# ProPrj_usb_hub_v2_2026-04-0__sche1.net
KiCad netlist of a schematic drawn in EasyEDA Pro
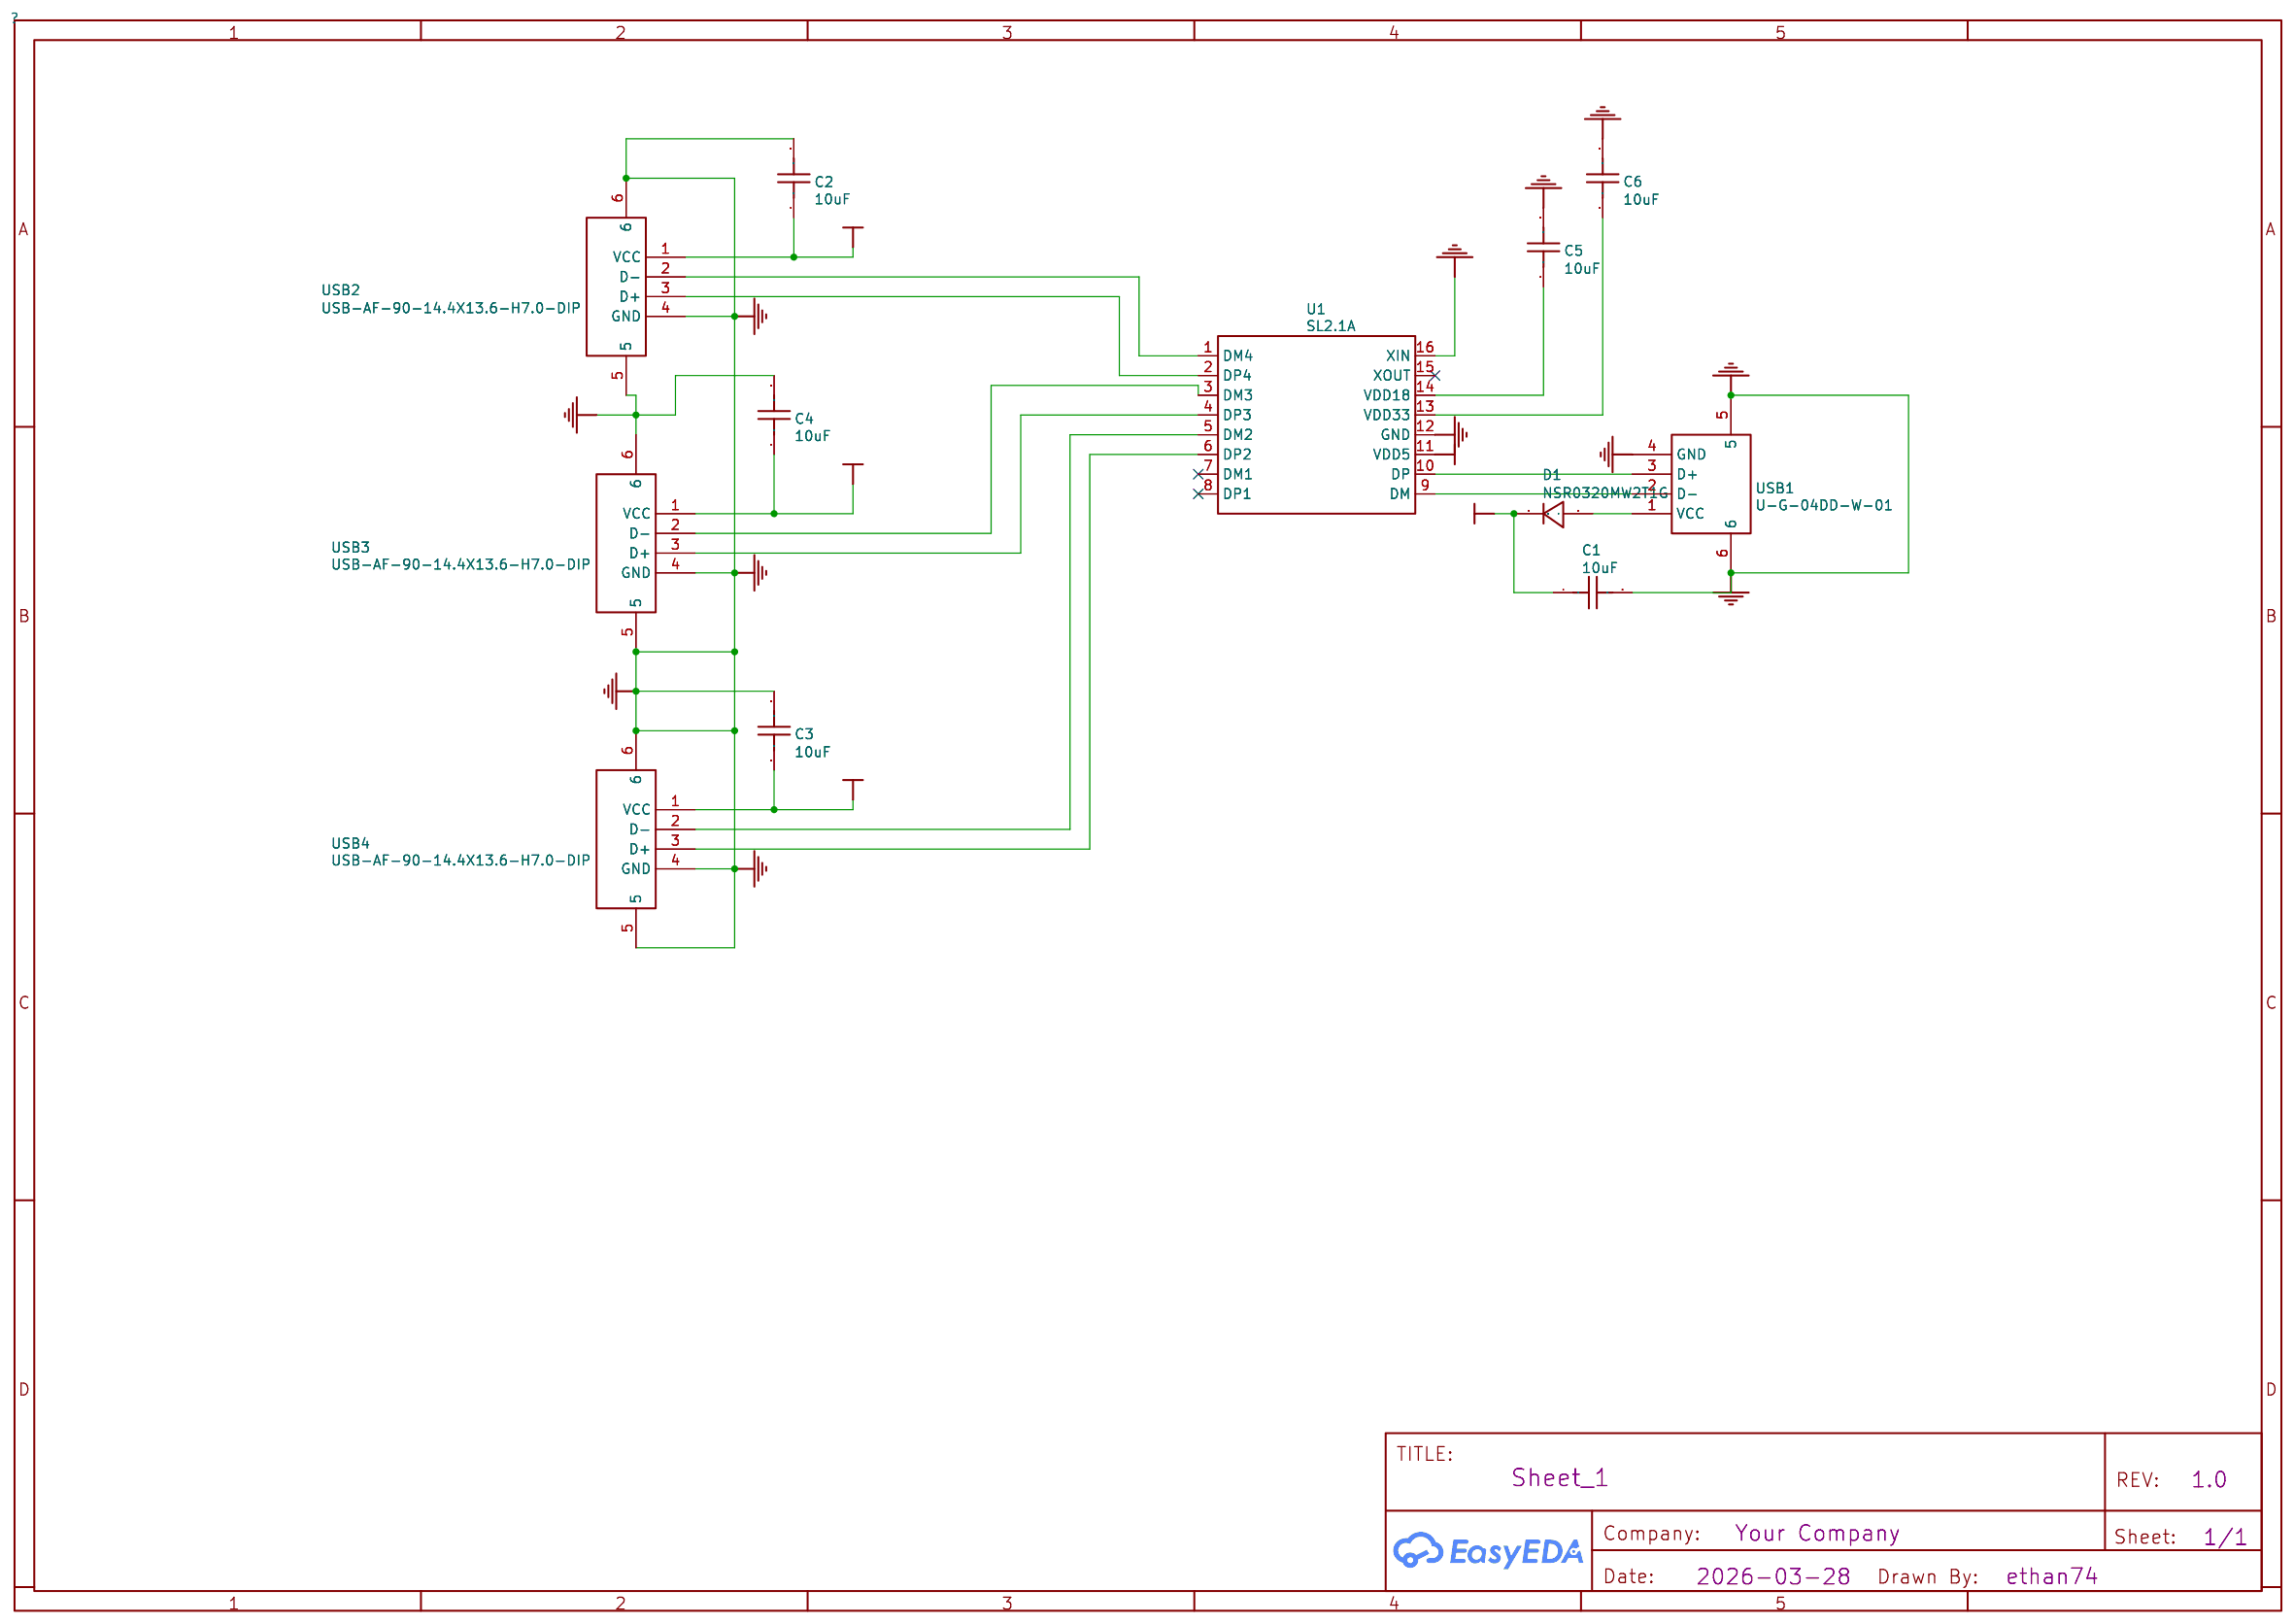
[diagram p0: schematic sheet]

(export (version "E")
  (design (tool "Eeschema 10.0.6"))
  (components
    (comp (ref "C1")
      (value "10uF")
      (footprint "easyedapro:C0603")
      (fields
        (field (name "Manufacturer Part") "CL10A106KP8NNNC")
        (field (name "Manufacturer") "SAMSUNG(三星)")
      )
      (libsource (lib "easyedapro") (part "10uF"))
    )
    (comp (ref "C2")
      (value "10uF")
      (footprint "easyedapro:C0603")
      (fields
        (field (name "Manufacturer Part") "CL10A106KP8NNNC")
        (field (name "Manufacturer") "SAMSUNG(三星)")
      )
      (libsource (lib "easyedapro") (part "10uF"))
    )
    (comp (ref "C3")
      (value "10uF")
      (footprint "easyedapro:C0603")
      (fields
        (field (name "Manufacturer Part") "CL10A106KP8NNNC")
        (field (name "Manufacturer") "SAMSUNG(三星)")
      )
      (libsource (lib "easyedapro") (part "10uF"))
    )
    (comp (ref "C4")
      (value "10uF")
      (footprint "easyedapro:C0603")
      (fields
        (field (name "Manufacturer Part") "CL10A106KP8NNNC")
        (field (name "Manufacturer") "SAMSUNG(三星)")
      )
      (libsource (lib "easyedapro") (part "10uF"))
    )
    (comp (ref "C5")
      (value "10uF")
      (footprint "easyedapro:C0603")
      (fields
        (field (name "Manufacturer Part") "CL10A106KP8NNNC")
        (field (name "Manufacturer") "SAMSUNG(三星)")
      )
      (libsource (lib "easyedapro") (part "10uF"))
    )
    (comp (ref "C6")
      (value "10uF")
      (footprint "easyedapro:C0603")
      (fields
        (field (name "Manufacturer Part") "CL10A106KP8NNNC")
        (field (name "Manufacturer") "SAMSUNG(三星)")
      )
      (libsource (lib "easyedapro") (part "10uF"))
    )
    (comp (ref "D1")
      (value "NSR0320MW2T1G")
      (footprint "easyedapro:SOD-323_L1.8-W1.3-LS2.5-RD")
      (fields (field (name "Manufacturer") "onsemi(安森美)"))
      (libsource (lib "easyedapro") (part "NSR0320MW2T1G"))
    )
    (comp (ref "U1")
      (value "SL2.1A")
      (footprint "easyedapro:SOP-16_L10.0-W3.9-P1.27-LS6.0-BL")
      (fields (field (name "Manufacturer") "CoreChips(和芯润德)") (field (name "Contributor") "LCSC"))
      (libsource (lib "easyedapro") (part "SL2.1A"))
    )
    (comp (ref "USB1")
      (value "U-G-04DD-W-01")
      (footprint "easyedapro:USB-A-TH_U-G-04WD-W-01")
      (fields (field (name "Manufacturer Part") "U-G-O4DD-W-1") (field (name "Manufacturer") "韩国韩荣"))
      (libsource (lib "easyedapro") (part "U-G-04DD-W-01"))
    )
    (comp (ref "USB2")
      (value "USB-AF-90-14.4X13.6-H7.0-DIP")
      (footprint "easyedapro:USB-A-TH_C46407")
      (fields
        (field (name "Manufacturer Part") "903-131A1011D10100")
        (field (name "Manufacturer") "精拓金")
        (field (name "Contributor") "LCSC")
      )
      (libsource (lib "easyedapro") (part "USB-AF-90-14.4X13.6-H7.0-DIP"))
    )
    (comp (ref "USB3")
      (value "USB-AF-90-14.4X13.6-H7.0-DIP")
      (footprint "easyedapro:USB-A-TH_C46407")
      (fields
        (field (name "Manufacturer Part") "903-131A1011D10100")
        (field (name "Manufacturer") "精拓金")
        (field (name "Contributor") "LCSC")
      )
      (libsource (lib "easyedapro") (part "USB-AF-90-14.4X13.6-H7.0-DIP"))
    )
    (comp (ref "USB4")
      (value "USB-AF-90-14.4X13.6-H7.0-DIP")
      (footprint "easyedapro:USB-A-TH_C46407")
      (fields
        (field (name "Manufacturer Part") "903-131A1011D10100")
        (field (name "Manufacturer") "精拓金")
        (field (name "Contributor") "LCSC")
      )
      (libsource (lib "easyedapro") (part "USB-AF-90-14.4X13.6-H7.0-DIP"))
    )
  )
  (nets
    (net (code "1") (name "+5V") (class "Default")
      (node (ref "C1") (pin "1") (pinfunction "1_1") (pintype "unspecified"))
      (node (ref "C2") (pin "1") (pinfunction "1_1") (pintype "unspecified"))
      (node (ref "C3") (pin "1") (pinfunction "1_1") (pintype "unspecified"))
      (node (ref "C4") (pin "1") (pinfunction "1_1") (pintype "unspecified"))
      (node (ref "D1") (pin "1") (pinfunction "C_1") (pintype "unspecified"))
      (node (ref "U1") (pin "11") (pinfunction "VDD5_11") (pintype "unspecified"))
      (node (ref "USB2") (pin "1") (pinfunction "VCC_1") (pintype "unspecified"))
      (node (ref "USB3") (pin "1") (pinfunction "VCC_1") (pintype "unspecified"))
      (node (ref "USB4") (pin "1") (pinfunction "VCC_1") (pintype "unspecified"))
    )
    (net (code "2") (name "GND") (class "Default")
      (node (ref "C1") (pin "2") (pinfunction "2_2") (pintype "unspecified"))
      (node (ref "C2") (pin "2") (pinfunction "2_2") (pintype "unspecified"))
      (node (ref "C3") (pin "2") (pinfunction "2_2") (pintype "unspecified"))
      (node (ref "C4") (pin "2") (pinfunction "2_2") (pintype "unspecified"))
      (node (ref "C5") (pin "2") (pinfunction "2_2") (pintype "unspecified"))
      (node (ref "C6") (pin "2") (pinfunction "2_2") (pintype "unspecified"))
      (node (ref "U1") (pin "12") (pinfunction "GND_12") (pintype "unspecified"))
      (node (ref "U1") (pin "16") (pinfunction "XIN_16") (pintype "unspecified"))
      (node (ref "USB1") (pin "4") (pinfunction "GND_4") (pintype "unspecified"))
      (node (ref "USB1") (pin "5") (pinfunction "5_5") (pintype "unspecified"))
      (node (ref "USB1") (pin "6") (pinfunction "6_6") (pintype "unspecified"))
      (node (ref "USB2") (pin "4") (pinfunction "GND_4") (pintype "unspecified"))
      (node (ref "USB2") (pin "5") (pinfunction "5_5") (pintype "unspecified"))
      (node (ref "USB2") (pin "6") (pinfunction "6_6") (pintype "unspecified"))
      (node (ref "USB3") (pin "4") (pinfunction "GND_4") (pintype "unspecified"))
      (node (ref "USB3") (pin "5") (pinfunction "5_5") (pintype "unspecified"))
      (node (ref "USB3") (pin "6") (pinfunction "6_6") (pintype "unspecified"))
      (node (ref "USB4") (pin "4") (pinfunction "GND_4") (pintype "unspecified"))
      (node (ref "USB4") (pin "5") (pinfunction "5_5") (pintype "unspecified"))
      (node (ref "USB4") (pin "6") (pinfunction "6_6") (pintype "unspecified"))
    )
    (net (code "3") (name "Net-(D1-A)") (class "Default")
      (node (ref "D1") (pin "2") (pinfunction "A_2") (pintype "unspecified"))
      (node (ref "USB1") (pin "1") (pinfunction "VCC_1") (pintype "unspecified"))
    )
    (net (code "4") (name "Net-(U1-DM)") (class "Default")
      (node (ref "U1") (pin "9") (pinfunction "DM_9") (pintype "unspecified"))
      (node (ref "USB1") (pin "2") (pinfunction "D-_2") (pintype "unspecified"))
    )
    (net (code "5") (name "Net-(U1-DM2)") (class "Default")
      (node (ref "U1") (pin "5") (pinfunction "DM2_5") (pintype "unspecified"))
      (node (ref "USB4") (pin "2") (pinfunction "D-_2") (pintype "unspecified"))
    )
    (net (code "6") (name "Net-(U1-DM3)") (class "Default")
      (node (ref "U1") (pin "3") (pinfunction "DM3_3") (pintype "unspecified"))
      (node (ref "USB3") (pin "2") (pinfunction "D-_2") (pintype "unspecified"))
    )
    (net (code "7") (name "Net-(U1-DM4)") (class "Default")
      (node (ref "U1") (pin "1") (pinfunction "DM4_1") (pintype "unspecified"))
      (node (ref "USB2") (pin "2") (pinfunction "D-_2") (pintype "unspecified"))
    )
    (net (code "8") (name "Net-(U1-DP)") (class "Default")
      (node (ref "U1") (pin "10") (pinfunction "DP_10") (pintype "unspecified"))
      (node (ref "USB1") (pin "3") (pinfunction "D+_3") (pintype "unspecified"))
    )
    (net (code "9") (name "Net-(U1-DP2)") (class "Default")
      (node (ref "U1") (pin "6") (pinfunction "DP2_6") (pintype "unspecified"))
      (node (ref "USB4") (pin "3") (pinfunction "D+_3") (pintype "unspecified"))
    )
    (net (code "10") (name "Net-(U1-DP3)") (class "Default")
      (node (ref "U1") (pin "4") (pinfunction "DP3_4") (pintype "unspecified"))
      (node (ref "USB3") (pin "3") (pinfunction "D+_3") (pintype "unspecified"))
    )
    (net (code "11") (name "Net-(U1-DP4)") (class "Default")
      (node (ref "U1") (pin "2") (pinfunction "DP4_2") (pintype "unspecified"))
      (node (ref "USB2") (pin "3") (pinfunction "D+_3") (pintype "unspecified"))
    )
    (net (code "12") (name "Net-(U1-VDD18)") (class "Default")
      (node (ref "C5") (pin "1") (pinfunction "1_1") (pintype "unspecified"))
      (node (ref "U1") (pin "14") (pinfunction "VDD18_14") (pintype "unspecified"))
    )
    (net (code "13") (name "Net-(U1-VDD33)") (class "Default")
      (node (ref "C6") (pin "1") (pinfunction "1_1") (pintype "unspecified"))
      (node (ref "U1") (pin "13") (pinfunction "VDD33_13") (pintype "unspecified"))
    )
    (net (code "14") (name "unconnected-(U1-DM1-Pad7)") (class "Default")
      (node (ref "U1") (pin "7") (pinfunction "DM1_7") (pintype "unspecified+no_connect"))
    )
    (net (code "15") (name "unconnected-(U1-DP1-Pad8)") (class "Default")
      (node (ref "U1") (pin "8") (pinfunction "DP1_8") (pintype "unspecified+no_connect"))
    )
    (net (code "16") (name "unconnected-(U1-XOUT-Pad15)") (class "Default")
      (node (ref "U1") (pin "15") (pinfunction "XOUT_15") (pintype "unspecified+no_connect"))
    )
  )
)
